# Board-PowerSupply.net
KiCad netlist of a schematic drawn in Altium Designer
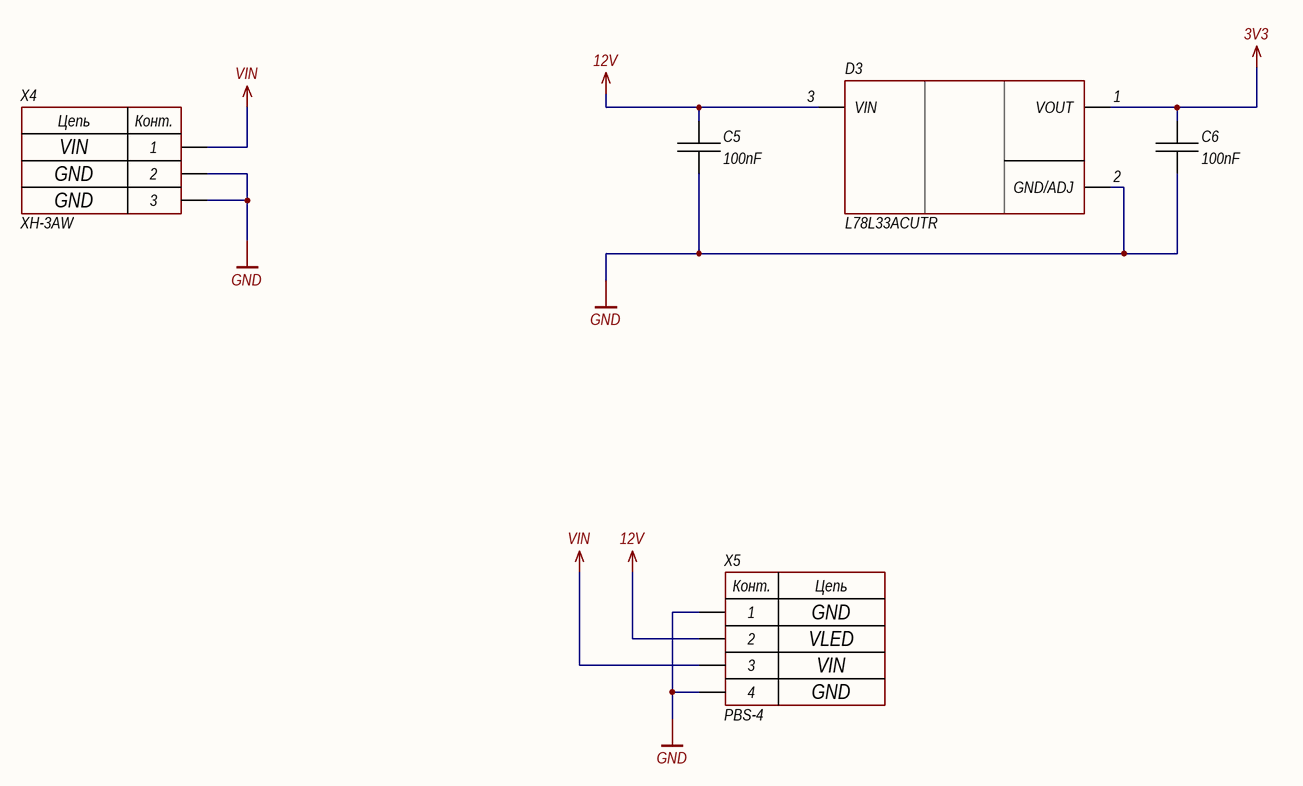
[diagram p0: Board-PowerSupply.SchDoc]

(export (version "E")
  (design (tool "Eeschema 10.0.6"))
  (components
    (comp (ref "C5")
      (value "100nF")
      (footprint "CH0402C")
      (fields (field (name "MANUFACTURER") "CCTC"))
      (libsource (lib "Discrete") (part "Capacitor"))
    )
    (comp (ref "C6")
      (value "100nF")
      (footprint "CH0402C")
      (fields (field (name "MANUFACTURER") "CCTC"))
      (libsource (lib "Discrete") (part "Capacitor"))
    )
    (comp (ref "D3")
      (value "L78L33ACUTR")
      (footprint "SOT89_123")
      (description "Step-down")
      (fields (field (name "MANUFACTURER") "ST Microelectronics"))
      (libsource (lib "Power Supplies") (part "L78LxxACUTR"))
    )
    (comp (ref "X4")
      (value "XH-3AW")
      (footprint "CON: XH-3AW")
      (libsource (lib "Connectors") (part "3-Connector"))
    )
    (comp (ref "X5")
      (value "PBS-4")
      (footprint "CON: PBS-4")
      (libsource (lib "Connectors") (part "4-Connector"))
    )
  )
  (nets
    (net (code "1") (name "3V3") (class "Default")
      (node (ref "C6") (pin "2") (pinfunction "2_2") (pintype "power_in"))
      (node (ref "D3") (pin "1") (pinfunction "VOUT_1") (pintype "power_in"))
    )
    (net (code "2") (name "12V") (class "Default")
      (node (ref "C5") (pin "2") (pinfunction "2_2") (pintype "power_in"))
      (node (ref "D3") (pin "3") (pinfunction "VIN_3") (pintype "power_in"))
      (node (ref "X5") (pin "2") (pinfunction "2_2") (pintype "passive"))
    )
    (net (code "3") (name "GND") (class "Default")
      (node (ref "C5") (pin "1") (pinfunction "1_1") (pintype "power_in"))
      (node (ref "C6") (pin "1") (pinfunction "1_1") (pintype "power_in"))
      (node (ref "D3") (pin "2") (pinfunction "GND/ADJ_2") (pintype "power_in"))
      (node (ref "X4") (pin "2") (pinfunction "2_2") (pintype "passive"))
      (node (ref "X4") (pin "3") (pinfunction "3_3") (pintype "passive"))
      (node (ref "X5") (pin "1") (pinfunction "1_1") (pintype "passive"))
      (node (ref "X5") (pin "4") (pinfunction "4_4") (pintype "passive"))
    )
    (net (code "4") (name "VIN") (class "Default")
      (node (ref "X4") (pin "1") (pinfunction "1_1") (pintype "passive"))
      (node (ref "X5") (pin "3") (pinfunction "3_3") (pintype "passive"))
    )
  )
)
